# oshi-fuse-board-mk-1_mini-ato.net
KiCad netlist of a schematic drawn in EAGLE
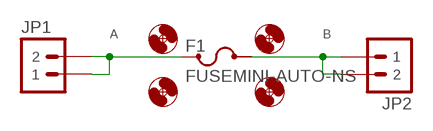
[diagram p0: schematic, sheet 1]

(export (version "E")
  (design (tool "Eeschema 10.0.6"))
  (components
    (comp (ref "F1")
      (value "FUSEMINI-AUTO-NS")
      (footprint "eagle-import:KEYSTONE-MINI-AUTO-FUSE-HOLDER-NS")
      (libsource (lib "eagle-import") (part "FUSEMINI-AUTO-NS"))
    )
    (comp (ref "H1")
      (value "HOLE#2")
      (footprint "eagle-import:HOLE-#2")
      (libsource (lib "eagle-import") (part "HOLE#2"))
    )
    (comp (ref "H2")
      (value "HOLE#2")
      (footprint "eagle-import:HOLE-#2")
      (libsource (lib "eagle-import") (part "HOLE#2"))
    )
    (comp (ref "H3")
      (value "HOLE#2")
      (footprint "eagle-import:HOLE-#2")
      (libsource (lib "eagle-import") (part "HOLE#2"))
    )
    (comp (ref "H4")
      (value "HOLE#2")
      (footprint "eagle-import:HOLE-#2")
      (libsource (lib "eagle-import") (part "HOLE#2"))
    )
    (comp (ref "JP1")
      (value "M023.5MM")
      (footprint "eagle-import:SCREWTERMINAL-3.5MM-2")
      (libsource (lib "eagle-import") (part "M023.5MM"))
    )
    (comp (ref "JP2")
      (value "M023.5MM")
      (footprint "eagle-import:SCREWTERMINAL-3.5MM-2")
      (libsource (lib "eagle-import") (part "M023.5MM"))
    )
  )
  (nets
    (net (code "1") (name "/A") (class "Default")
      (node (ref "F1") (pin "P1@1") (pinfunction "1_P1@1") (pintype "passive"))
      (node (ref "F1") (pin "P1@2") (pinfunction "1_P1@2") (pintype "passive"))
      (node (ref "JP1") (pin "1") (pinfunction "1_1") (pintype "passive"))
      (node (ref "JP1") (pin "2") (pinfunction "2_2") (pintype "passive"))
    )
    (net (code "2") (name "/B") (class "Default")
      (node (ref "F1") (pin "P2@1") (pinfunction "2_P2@1") (pintype "passive"))
      (node (ref "F1") (pin "P2@2") (pinfunction "2_P2@2") (pintype "passive"))
      (node (ref "JP2") (pin "1") (pinfunction "1_1") (pintype "passive"))
      (node (ref "JP2") (pin "2") (pinfunction "2_2") (pintype "passive"))
    )
  )
)
